# tesis_page2_arm.net
KiCad netlist of a schematic drawn in Altium Designer
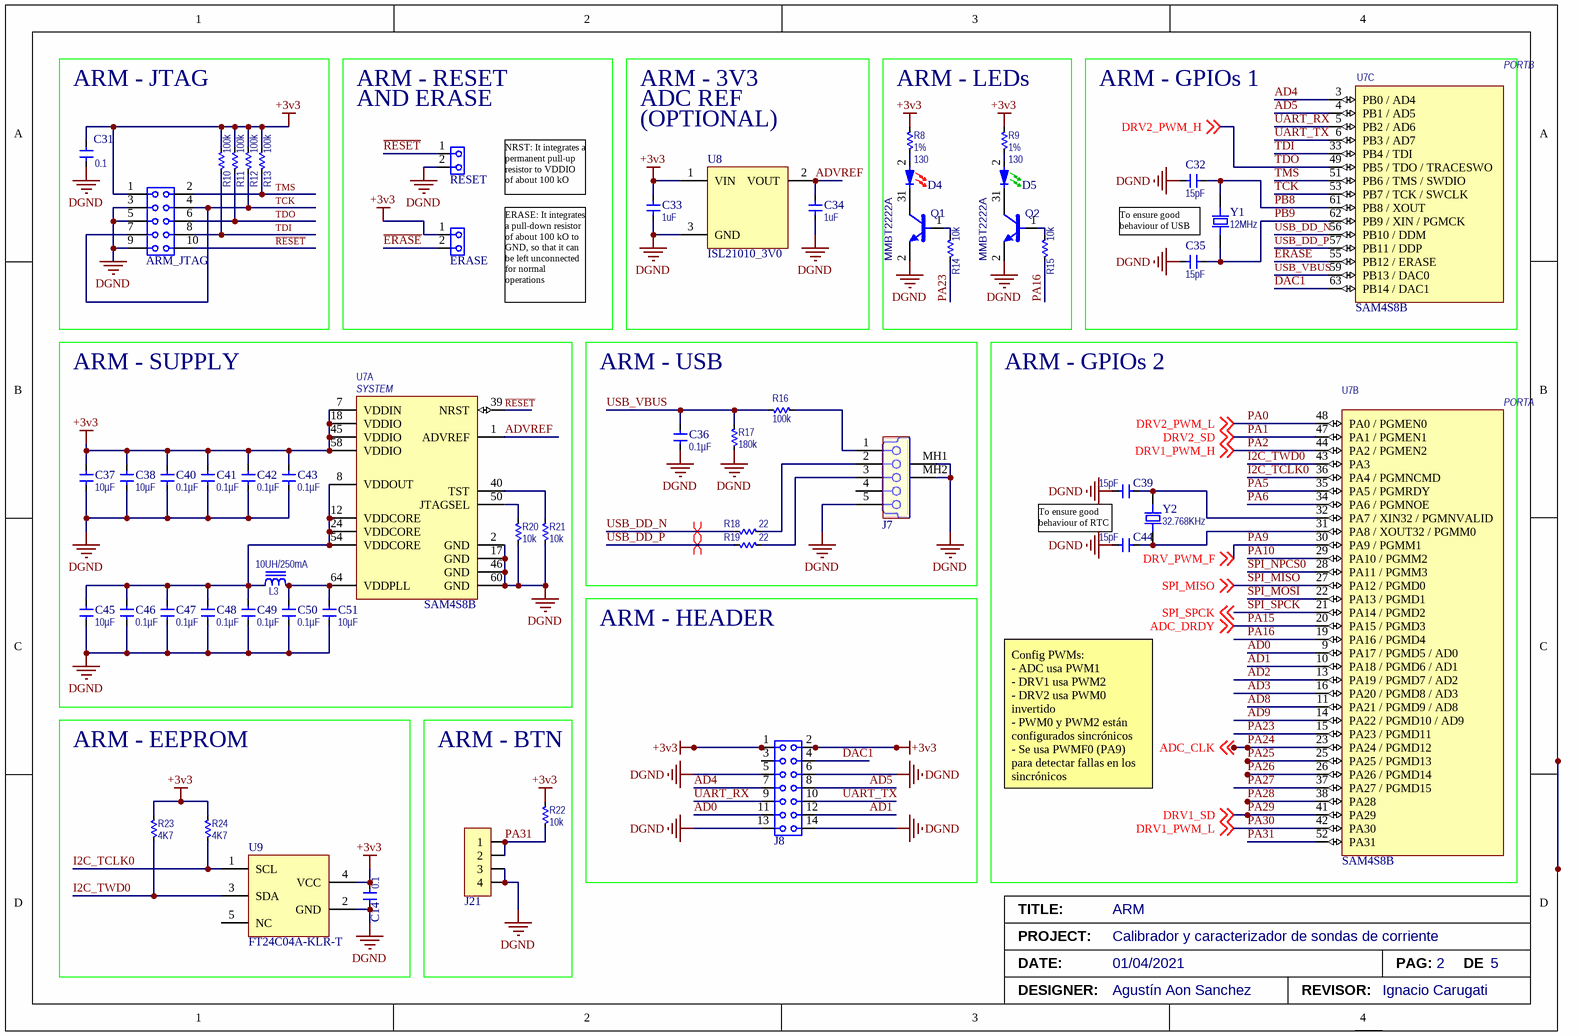
[diagram p0: tesis_page2_arm.SchDoc]

(export (version "E")
  (design (tool "Eeschema 10.0.6"))
  (components
    (comp (ref "ARM_JTAG")
      (value "CON_20021121-00010C4LF_FCI")
      (footprint "FCI_20021121-00010C4LF")
      (description "CONN HEADER 10POS DL UNSHRD SMD")
      (fields (field (name "MANUFACTURER") "FCI") (field (name "DIGIKEY PART NUMBER") "609-3695-1-ND"))
      (libsource (lib "pqm_v2_lib_connectors") (part "CON_20021121-00010C4LF_FCI"))
    )
    (comp (ref "C14")
      (value "0.1")
      (footprint "CAPC2013X110N")
      (description "CAP CER 0.1UF 25V 10% X7R 0805")
      (fields (field (name "MANUFACTURER") "Yageo") (field (name "TOLERANCE") "10%"))
      (libsource (lib "pqm_v2_lib_cap") (part "CAP_CC0805KRX7R8BB104_YAGEO"))
    )
    (comp (ref "C31")
      (value "0.1")
      (footprint "CAPC2013X110N")
      (description "CAP CER 0.1UF 25V 10% X7R 0805")
      (fields (field (name "MANUFACTURER") "Yageo") (field (name "TOLERANCE") "10%"))
      (libsource (lib "pqm_v2_lib_cap") (part "CAP_CC0805KRX7R8BB104_YAGEO"))
    )
    (comp (ref "C32")
      (value "15pF")
      (footprint "CAPC2013X110N")
      (description "CAP CER 15PF 50V NP0 0805")
      (fields (field (name "MANUFACTURER") "Kemet") (field (name "DIGIKEY PART NUMBER") "399-7428-1-ND"))
      (libsource (lib "pqm_v2_lib_cap") (part "CAP_C0805X150J5GACTU_KEMET"))
    )
    (comp (ref "C33")
      (value "1uF")
      (footprint "CAPC2013X110N")
      (description "CAP CER 1UF 16V X7R 0805")
      (fields (field (name "MANUFACTURER") "YAGEO") (field (name "TOLERANCE") "10%"))
      (libsource (lib "pqm_v2_lib_cap") (part "CAP_CC0805KKX7R7BB105_YAGEO"))
    )
    (comp (ref "C34")
      (value "1uF")
      (footprint "CAPC2013X110N")
      (description "CAP CER 1UF 16V X7R 0805")
      (fields (field (name "MANUFACTURER") "YAGEO") (field (name "TOLERANCE") "10%"))
      (libsource (lib "pqm_v2_lib_cap") (part "CAP_CC0805KKX7R7BB105_YAGEO"))
    )
    (comp (ref "C35")
      (value "15pF")
      (footprint "CAPC2013X110N")
      (description "CAP CER 15PF 50V NP0 0805")
      (fields (field (name "MANUFACTURER") "Kemet") (field (name "DIGIKEY PART NUMBER") "399-7428-1-ND"))
      (libsource (lib "pqm_v2_lib_cap") (part "CAP_C0805X150J5GACTU_KEMET"))
    )
    (comp (ref "C36")
      (value "0.1µF")
      (footprint "CAPC2013X110N")
      (description "CAP CER 0.1UF 25V 10% X7R 0805")
      (fields (field (name "MANUFACTURER") "Yageo") (field (name "TOLERANCE") "10%"))
      (libsource (lib "pqm_v2_lib_cap") (part "CAP_CC0805KRX7R8BB104_YAGEO"))
    )
    (comp (ref "C37")
      (value "10µF")
      (footprint "CAPC2013X110N")
      (description "CAP CER 10UF 16V X5R 0805")
      (fields (field (name "MANUFACTURER") "Samsung") (field (name "TOLERANCE") "10%"))
      (libsource (lib "lib_ic_CAP") (part "CAP_CL21A106KOCL3RC"))
    )
    (comp (ref "C38")
      (value "10µF")
      (footprint "CAPC2013X110N")
      (description "CAP CER 10UF 16V X5R 0805")
      (fields (field (name "MANUFACTURER") "Samsung") (field (name "TOLERANCE") "10%"))
      (libsource (lib "lib_ic_CAP") (part "CAP_CL21A106KOCL3RC"))
    )
    (comp (ref "C39")
      (value "15pF")
      (footprint "CAPC2013X110N")
      (description "CAP CER 15PF 50V NP0 0805")
      (fields (field (name "MANUFACTURER") "Kemet") (field (name "DIGIKEY PART NUMBER") "399-7428-1-ND"))
      (libsource (lib "pqm_v2_lib_cap") (part "CAP_C0805X150J5GACTU_KEMET"))
    )
    (comp (ref "C40")
      (value "0.1µF")
      (footprint "CAPC2013X110N")
      (description "CAP CER 0.1UF 25V 10% X7R 0805")
      (fields (field (name "MANUFACTURER") "Yageo") (field (name "TOLERANCE") "10%"))
      (libsource (lib "pqm_v2_lib_cap") (part "CAP_CC0805KRX7R8BB104_YAGEO"))
    )
    (comp (ref "C41")
      (value "0.1µF")
      (footprint "CAPC2013X110N")
      (description "CAP CER 0.1UF 25V 10% X7R 0805")
      (fields (field (name "MANUFACTURER") "Yageo") (field (name "TOLERANCE") "10%"))
      (libsource (lib "pqm_v2_lib_cap") (part "CAP_CC0805KRX7R8BB104_YAGEO"))
    )
    (comp (ref "C42")
      (value "0.1µF")
      (footprint "CAPC2013X110N")
      (description "CAP CER 0.1UF 25V 10% X7R 0805")
      (fields (field (name "MANUFACTURER") "Yageo") (field (name "TOLERANCE") "10%"))
      (libsource (lib "pqm_v2_lib_cap") (part "CAP_CC0805KRX7R8BB104_YAGEO"))
    )
    (comp (ref "C43")
      (value "0.1µF")
      (footprint "CAPC2013X110N")
      (description "CAP CER 0.1UF 25V 10% X7R 0805")
      (fields (field (name "MANUFACTURER") "Yageo") (field (name "TOLERANCE") "10%"))
      (libsource (lib "pqm_v2_lib_cap") (part "CAP_CC0805KRX7R8BB104_YAGEO"))
    )
    (comp (ref "C44")
      (value "15pF")
      (footprint "CAPC2013X110N")
      (description "CAP CER 15PF 50V NP0 0805")
      (fields (field (name "MANUFACTURER") "Kemet") (field (name "DIGIKEY PART NUMBER") "399-7428-1-ND"))
      (libsource (lib "pqm_v2_lib_cap") (part "CAP_C0805X150J5GACTU_KEMET"))
    )
    (comp (ref "C45")
      (value "10µF")
      (footprint "CAPC2013X110N")
      (description "CAP CER 10UF 16V X5R 0805")
      (fields (field (name "MANUFACTURER") "Samsung") (field (name "TOLERANCE") "10%"))
      (libsource (lib "lib_ic_CAP") (part "CAP_CL21A106KOCL3RC"))
    )
    (comp (ref "C46")
      (value "0.1µF")
      (footprint "CAPC2013X110N")
      (description "CAP CER 0.1UF 25V 10% X7R 0805")
      (fields (field (name "MANUFACTURER") "Yageo") (field (name "TOLERANCE") "10%"))
      (libsource (lib "pqm_v2_lib_cap") (part "CAP_CC0805KRX7R8BB104_YAGEO"))
    )
    (comp (ref "C47")
      (value "0.1µF")
      (footprint "CAPC2013X110N")
      (description "CAP CER 0.1UF 25V 10% X7R 0805")
      (fields (field (name "MANUFACTURER") "Yageo") (field (name "TOLERANCE") "10%"))
      (libsource (lib "pqm_v2_lib_cap") (part "CAP_CC0805KRX7R8BB104_YAGEO"))
    )
    (comp (ref "C48")
      (value "0.1µF")
      (footprint "CAPC2013X110N")
      (description "CAP CER 0.1UF 25V 10% X7R 0805")
      (fields (field (name "MANUFACTURER") "Yageo") (field (name "TOLERANCE") "10%"))
      (libsource (lib "pqm_v2_lib_cap") (part "CAP_CC0805KRX7R8BB104_YAGEO"))
    )
    (comp (ref "C49")
      (value "0.1µF")
      (footprint "CAPC2013X110N")
      (description "CAP CER 0.1UF 25V 10% X7R 0805")
      (fields (field (name "MANUFACTURER") "Yageo") (field (name "TOLERANCE") "10%"))
      (libsource (lib "pqm_v2_lib_cap") (part "CAP_CC0805KRX7R8BB104_YAGEO"))
    )
    (comp (ref "C50")
      (value "0.1µF")
      (footprint "CAPC2013X110N")
      (description "CAP CER 0.1UF 25V 10% X7R 0805")
      (fields (field (name "MANUFACTURER") "Yageo") (field (name "TOLERANCE") "10%"))
      (libsource (lib "pqm_v2_lib_cap") (part "CAP_CC0805KRX7R8BB104_YAGEO"))
    )
    (comp (ref "C51")
      (value "10µF")
      (footprint "CAPC2013X110N")
      (description "CAP CER 10UF 16V X5R 0805")
      (fields (field (name "MANUFACTURER") "Samsung") (field (name "TOLERANCE") "10%"))
      (libsource (lib "lib_ic_CAP") (part "CAP_CL21A106KOCL3RC"))
    )
    (comp (ref "D4")
      (value "DIO_150080RS75000_WURTH")
      (footprint "DIO0805")
      (description "LED RED CLEAR 0805 SMD")
      (fields
        (field (name "MANUFACTURER") "Wurth Electronics Inc.")
        (field (name "MANUFACTURER PART NUMBER") "150080RS75000")
      )
      (libsource (lib "lib_ic_DIO") (part "DIO_150080RS75000_WURTH"))
    )
    (comp (ref "D5")
      (value "DIO_150080VS75000_WURTH")
      (footprint "DIO0805")
      (description "LED GREEN CLEAR 0805 SMD")
      (fields
        (field (name "MANUFACTURER") "Wurth Electronics Inc.")
        (field (name "MANUFACTURER PART NUMBER") "150080VS75000")
      )
      (libsource (lib "lib_ic_DIO") (part "DIO_150080VS75000_WURTH"))
    )
    (comp (ref "ERASE")
      (value "CON_Header_1x2")
      (footprint "RAD2")
      (libsource (lib "lib_ic_CON") (part "CON_Header_1x2"))
    )
    (comp (ref "J7")
      (value "CON_MINI_USB")
      (footprint "UBS MiniB")
      (description "CONN RCPT MINI USB2.0 5POS SLD")
      (fields
        (field (name "DIGIKEY PART NUMBER") "H11589CT-ND")
        (field (name "MANUFACTURER PART NUMBER") "UX60SC-MB-5S8")
      )
      (libsource (lib "lib_ic_CON") (part "CON_MINI_USB"))
    )
    (comp (ref "J8")
      (value "CON_Header_CAL_1")
      (footprint "HeaderCAL_1")
      (libsource (lib "lib_ic_CON") (part "CON_Header_CAL_1"))
    )
    (comp (ref "J21")
      (value "MSC_B3F-1000_OMRON")
      (footprint "SW_1825910-6")
      (description "SWITCH TACTILE SPST-NO 0.05A 24V")
      (fields
        (field (name "MOUSER PART NUMBER") "653-B3F-1000")
        (field (name "MANUFACTURER PART NUMBER") "B3F-1000")
      )
      (libsource (lib "lib_ic_MSC") (part "MSC_B3F-1000_OMRON"))
    )
    (comp (ref "L3")
      (value "10UH/250mA")
      (footprint "INDC4532X170N")
      (description "FIXED IND 10UH 250mA 1.6 OHM SMD")
      (fields
        (field (name "MANUFACTURER") "Bourns Inc")
        (field (name "DIGIKEY PART NUMBER") "CM453232-100KLCT-ND")
      )
      (libsource (lib "lib_ic_MAG") (part "MAG_PM1812-100J-RC"))
    )
    (comp (ref "Q1")
      (value "MMBT2222A")
      (footprint "SOT23-3M")
      (description "TRANS NPN 40V 0.6A SMD SOT23-3")
      (fields
        (field (name "MOUSER PART NUMBER") "621-MMBT2222A-F")
        (field (name "DIGIKEY PART NUMBER") "MMBT2222A-7-F")
      )
      (libsource (lib "lib_ic_TRAN") (part "Q_MMBT2222A-7-F_DIODES"))
    )
    (comp (ref "Q2")
      (value "MMBT2222A")
      (footprint "SOT23-3M")
      (description "TRANS NPN 40V 0.6A SMD SOT23-3")
      (fields
        (field (name "MOUSER PART NUMBER") "621-MMBT2222A-F")
        (field (name "DIGIKEY PART NUMBER") "MMBT2222A-7-F")
      )
      (libsource (lib "lib_ic_TRAN") (part "Q_MMBT2222A-7-F_DIODES"))
    )
    (comp (ref "R8")
      (value "130")
      (footprint "RESC2013X065BN")
      (description "RES SMD 130 OHM 1% 1/8W 0805")
      (fields
        (field (name "MANUFACTURER") "Yageo")
        (field (name "DIGIKEY PART NUMBER") "311-130CRCT-ND")
        (field (name "TOLERANCE") "1%")
      )
      (libsource (lib "lib_ic_RES") (part "RES_RC0805FR-07130RL_YAGEO"))
    )
    (comp (ref "R9")
      (value "130")
      (footprint "RESC2013X065BN")
      (description "RES SMD 130 OHM 1% 1/8W 0805")
      (fields
        (field (name "MANUFACTURER") "Yageo")
        (field (name "DIGIKEY PART NUMBER") "311-130CRCT-ND")
        (field (name "TOLERANCE") "1%")
      )
      (libsource (lib "lib_ic_RES") (part "RES_RC0805FR-07130RL_YAGEO"))
    )
    (comp (ref "R10")
      (value "100k")
      (footprint "RESC2013X065BN")
      (description "RES SMD 100K OHM 5% 1/8W 0805")
      (fields (field (name "TOLERANCE") "5%") (field (name "MANUFACTURER") "Yageo"))
      (libsource (lib "pqm_v2_lib_res") (part "RES_AC0805JR-07100KL_YAGEO"))
    )
    (comp (ref "R11")
      (value "100k")
      (footprint "RESC2013X065BN")
      (description "RES SMD 100K OHM 5% 1/8W 0805")
      (fields (field (name "TOLERANCE") "5%") (field (name "MANUFACTURER") "Yageo"))
      (libsource (lib "pqm_v2_lib_res") (part "RES_AC0805JR-07100KL_YAGEO"))
    )
    (comp (ref "R12")
      (value "100k")
      (footprint "RESC2013X065BN")
      (description "RES SMD 100K OHM 5% 1/8W 0805")
      (fields (field (name "TOLERANCE") "5%") (field (name "MANUFACTURER") "Yageo"))
      (libsource (lib "pqm_v2_lib_res") (part "RES_AC0805JR-07100KL_YAGEO"))
    )
    (comp (ref "R13")
      (value "100k")
      (footprint "RESC2013X065BN")
      (description "RES SMD 100K OHM 5% 1/8W 0805")
      (fields (field (name "TOLERANCE") "5%") (field (name "MANUFACTURER") "Yageo"))
      (libsource (lib "pqm_v2_lib_res") (part "RES_AC0805JR-07100KL_YAGEO"))
    )
    (comp (ref "R14")
      (value "10k")
      (footprint "RESC2013X065BN")
      (description "RES SMD 10K OHM 1% 1/8W 0805")
      (fields (field (name "MANUFACTURER") "Yageo") (field (name "DIGIKEY PART NUMBER") "311-10.0KCRCT-ND"))
      (libsource (lib "lib_ic_RES") (part "RES_RC0805FR-0710KL_YAGEO"))
    )
    (comp (ref "R15")
      (value "10k")
      (footprint "RESC2013X065BN")
      (description "RES SMD 10K OHM 1% 1/8W 0805")
      (fields (field (name "MANUFACTURER") "Yageo") (field (name "DIGIKEY PART NUMBER") "311-10.0KCRCT-ND"))
      (libsource (lib "lib_ic_RES") (part "RES_RC0805FR-0710KL_YAGEO"))
    )
    (comp (ref "R16")
      (value "100k")
      (footprint "RESC3216N")
      (description "RES SMD 100K OHM 5% 1/4W 1206")
      (fields (field (name "MANUFACTURER") "YAGEO") (field (name "TOLERANCE") "5%"))
      (libsource (lib "lib_ic_RES") (part "RES_RC1206JR-07100KL_YAGEO"))
    )
    (comp (ref "R17")
      (value "180k")
      (footprint "RESC3216N")
      (description "RES SMD 180K OHM 5% 1/4W 1206")
      (fields (field (name "MANUFACTURER") "YAGEO") (field (name "TOLERANCE") "5%"))
      (libsource (lib "lib_ic_RES") (part "RES_RC1206JR-07180KL_YAGEO"))
    )
    (comp (ref "R18")
      (value "22")
      (footprint "RESC2013X065BN")
      (description "RES SMD 22 OHM 5% 1/8W 0805")
      (fields (field (name "MANUFACTURER") "Yageo") (field (name "TOLERANCE") "5%"))
      (libsource (lib "lib_ic_RES") (part "RES_AC0805JR-0722RL_YAGEO"))
    )
    (comp (ref "R19")
      (value "22")
      (footprint "RESC2013X065BN")
      (description "RES SMD 22 OHM 5% 1/8W 0805")
      (fields (field (name "MANUFACTURER") "Yageo") (field (name "TOLERANCE") "5%"))
      (libsource (lib "lib_ic_RES") (part "RES_AC0805JR-0722RL_YAGEO"))
    )
    (comp (ref "R20")
      (value "10k")
      (footprint "RESC2013X065BN")
      (description "RES SMD 10K OHM 5% 1/8W 0805")
      (fields (field (name "TOLERANCE") "5%") (field (name "MANUFACTURER") "Yageo"))
      (libsource (lib "pqm_v2_lib_res") (part "RES_RC0805JR-0710KL_YAGEO"))
    )
    (comp (ref "R21")
      (value "10k")
      (footprint "RESC2013X065BN")
      (description "RES SMD 10K OHM 5% 1/8W 0805")
      (fields (field (name "TOLERANCE") "5%") (field (name "MANUFACTURER") "Yageo"))
      (libsource (lib "pqm_v2_lib_res") (part "RES_RC0805JR-0710KL_YAGEO"))
    )
    (comp (ref "R22")
      (value "10k")
      (footprint "RESC2013X065BN")
      (description "RES SMD 10K OHM 5% 1/8W 0805")
      (fields (field (name "TOLERANCE") "5%") (field (name "MANUFACTURER") "Yageo"))
      (libsource (lib "pqm_v2_lib_res") (part "RES_RC0805JR-0710KL_YAGEO"))
    )
    (comp (ref "R23")
      (value "4K7")
      (footprint "RESC2013X065BN")
      (description "RES SMD 4.7K OHM 1% 1/8W 0805")
      (fields (field (name "MANUFACTURER") "Yageo") (field (name "DIGIKEY PART NUMBER") "311-4.70KCRCT-ND"))
      (libsource (lib "lib_ic_RES") (part "RES_RC0805FR-074K7L_YAGEO"))
    )
    (comp (ref "R24")
      (value "4K7")
      (footprint "RESC2013X065BN")
      (description "RES SMD 4.7K OHM 1% 1/8W 0805")
      (fields (field (name "MANUFACTURER") "Yageo") (field (name "DIGIKEY PART NUMBER") "311-4.70KCRCT-ND"))
      (libsource (lib "lib_ic_RES") (part "RES_RC0805FR-074K7L_YAGEO"))
    )
    (comp (ref "RESET")
      (value "CON_Header_1x2")
      (footprint "RAD2")
      (libsource (lib "lib_ic_CON") (part "CON_Header_1x2"))
    )
    (comp (ref "U7")
      (value "SAM4S8B")
      (footprint "TQFP50P1000X1000X160-64N")
      (description "IC MCU 32BIT 512KB FLASH 64LQFP")
      (fields (field (name "MANUFACTURER") "Atmel") (field (name "DIGIKEY PART NUMBER") "ATSAM4S8BA-AU-ND"))
      (libsource (lib "") (part "IC_ATSAM4S8BA-AU_ATMEL_1"))
    )
    (comp (ref "U8")
      (value "ISL21010_3V0")
      (footprint "SOT23-3M")
      (description "IC VREF SERIES 3V SOT23-3")
      (fields
        (field (name "DIGIKEY PART NUMBER") "ISL21010CFH330Z-TKCT-ND")
        (field (name "MANUFACTURER PART NUMBER") "ISL21010CFH330Z-TK")
      )
      (libsource (lib "lib_ic_IC") (part "IC_ISL21010_3V0_INTERSIL"))
    )
    (comp (ref "U9")
      (value "FT24C04A-KLR-T")
      (footprint "SOT23-5AM")
      (fields (field (name "MANUFACTURER") "Fremont Micro Devices"))
      (libsource (lib "lib_ic_IC") (part "IC_FT24C04A-KLR-T"))
    )
    (comp (ref "Y1")
      (value "12MHz")
      (footprint "CSM-3X")
      (description "12 MHz ±30 ppm Cristales 20 pF 60 Ohm -10°C ~ 70°C Montaje en superficie HC49/US")
      (fields (field (name "MANUFACTURER") "ECS Inc.") (field (name "DIGIKEY PART NUMBER") "XC1770DKR-ND"))
      (libsource (lib "pqm_v2_lib_connectors") (part "MSC_ECS-120-20-3X-TR_ECS"))
    )
    (comp (ref "Y2")
      (value "32.768KHz")
      (footprint "XTAL3215X090N")
      (description "CRYSTAL 32.7680KHZ 12.5PF SMD")
      (fields (field (name "MANUFACTURER") "ECS") (field (name "DIGIKEY PART NUMBER") "XC1967CT-ND"))
      (libsource (lib "pqm_v2_lib_connectors") (part "MSC_ECS-.327-12.5-34S-TR_ECS"))
    )
  )
  (nets
    (net (code "1") (name "+3v3") (class "Default")
      (node (ref "ARM_JTAG") (pin "1") (pinfunction "1_1") (pintype "passive"))
      (node (ref "C14") (pin "2") (pinfunction "T2_2") (pintype "passive"))
      (node (ref "C31") (pin "1") (pinfunction "T1_1") (pintype "passive"))
      (node (ref "C33") (pin "1") (pinfunction "T1_1") (pintype "passive"))
      (node (ref "C37") (pin "2") (pinfunction "T2_2") (pintype "passive"))
      (node (ref "C38") (pin "2") (pinfunction "T2_2") (pintype "passive"))
      (node (ref "C40") (pin "2") (pinfunction "T2_2") (pintype "passive"))
      (node (ref "C41") (pin "2") (pinfunction "T2_2") (pintype "passive"))
      (node (ref "C42") (pin "2") (pinfunction "T2_2") (pintype "passive"))
      (node (ref "C43") (pin "2") (pinfunction "T2_2") (pintype "passive"))
      (node (ref "ERASE") (pin "1") (pinfunction "1_1") (pintype "passive"))
      (node (ref "J8") (pin "1") (pinfunction "1_1") (pintype "passive"))
      (node (ref "J8") (pin "2") (pinfunction "2_2") (pintype "passive"))
      (node (ref "R10") (pin "2") (pinfunction "T2_2") (pintype "passive"))
      (node (ref "R11") (pin "2") (pinfunction "T2_2") (pintype "passive"))
      (node (ref "R12") (pin "2") (pinfunction "T2_2") (pintype "passive"))
      (node (ref "R13") (pin "2") (pinfunction "T2_2") (pintype "passive"))
      (node (ref "R22") (pin "2") (pinfunction "T2_2") (pintype "passive"))
      (node (ref "R23") (pin "2") (pinfunction "T2_2") (pintype "passive"))
      (node (ref "R24") (pin "2") (pinfunction "T2_2") (pintype "passive"))
      (node (ref "R8") (pin "2") (pinfunction "T2_2") (pintype "passive"))
      (node (ref "R9") (pin "2") (pinfunction "T2_2") (pintype "passive"))
      (node (ref "U7") (pin "18") (pinfunction "VDDIO_18") (pintype "power_in"))
      (node (ref "U7") (pin "45") (pinfunction "VDDIO_45") (pintype "power_in"))
      (node (ref "U7") (pin "58") (pinfunction "VDDIO_58") (pintype "power_in"))
      (node (ref "U7") (pin "7") (pinfunction "VDDIN_7") (pintype "power_in"))
      (node (ref "U8") (pin "1") (pinfunction "VIN_1") (pintype "passive"))
      (node (ref "U9") (pin "4") (pinfunction "VCC_4") (pintype "passive"))
    )
    (net (code "2") (name "/AD0") (class "Default")
      (node (ref "J8") (pin "11") (pinfunction "11_11") (pintype "passive"))
      (node (ref "U7") (pin "9") (pinfunction "PA17_/_PGMD5_/_AD0_9") (pintype "bidirectional"))
    )
    (net (code "3") (name "/AD1") (class "Default")
      (node (ref "J8") (pin "12") (pinfunction "12_12") (pintype "passive"))
      (node (ref "U7") (pin "10") (pinfunction "PA18_/_PGMD6_/_AD1_10") (pintype "bidirectional"))
    )
    (net (code "4") (name "/AD2") (class "Default")
      (node (ref "U7") (pin "13") (pinfunction "PA19_/_PGMD7_/_AD2_13") (pintype "bidirectional"))
    )
    (net (code "5") (name "/AD3") (class "Default")
      (node (ref "U7") (pin "16") (pinfunction "PA20_/_PGMD8_/_AD3_16") (pintype "bidirectional"))
    )
    (net (code "6") (name "/AD4") (class "Default")
      (node (ref "J8") (pin "7") (pinfunction "7_7") (pintype "passive"))
      (node (ref "U7") (pin "3") (pinfunction "PB0_/_AD4_3") (pintype "bidirectional"))
    )
    (net (code "7") (name "/AD5") (class "Default")
      (node (ref "J8") (pin "8") (pinfunction "8_8") (pintype "passive"))
      (node (ref "U7") (pin "4") (pinfunction "PB1_/_AD5_4") (pintype "bidirectional"))
    )
    (net (code "8") (name "/AD8") (class "Default")
      (node (ref "U7") (pin "11") (pinfunction "PA21_/_PGMD9_/_AD8_11") (pintype "bidirectional"))
    )
    (net (code "9") (name "/AD9") (class "Default")
      (node (ref "U7") (pin "14") (pinfunction "PA22_/_PGMD10_/_AD9_14") (pintype "bidirectional"))
    )
    (net (code "10") (name "/ADVREF") (class "Default")
      (node (ref "C34") (pin "1") (pinfunction "T1_1") (pintype "passive"))
      (node (ref "U7") (pin "1") (pinfunction "ADVREF_1") (pintype "power_in"))
      (node (ref "U8") (pin "2") (pinfunction "VOUT_2") (pintype "passive"))
    )
    (net (code "11") (name "/DAC1") (class "Default")
      (node (ref "J8") (pin "4") (pinfunction "4_4") (pintype "passive"))
      (node (ref "U7") (pin "63") (pinfunction "PB14_/_DAC1_63") (pintype "bidirectional"))
    )
    (net (code "12") (name "/I2C_TCLK0") (class "Default")
      (node (ref "R24") (pin "1") (pinfunction "T1_1") (pintype "passive"))
      (node (ref "U7") (pin "36") (pinfunction "PA4_/_PGMNCMD_36") (pintype "bidirectional"))
      (node (ref "U9") (pin "1") (pinfunction "SCL_1") (pintype "passive"))
    )
    (net (code "13") (name "/I2C_TWD0") (class "Default")
      (node (ref "R23") (pin "1") (pinfunction "T1_1") (pintype "passive"))
      (node (ref "U7") (pin "43") (pinfunction "PA3_43") (pintype "bidirectional"))
      (node (ref "U9") (pin "3") (pinfunction "SDA_3") (pintype "passive"))
    )
    (net (code "14") (name "/PA5") (class "Default")
      (node (ref "U7") (pin "35") (pinfunction "PA5_/_PGMRDY_35") (pintype "bidirectional"))
    )
    (net (code "15") (name "/PA6") (class "Default")
      (node (ref "U7") (pin "34") (pinfunction "PA6_/_PGMNOE_34") (pintype "bidirectional"))
    )
    (net (code "16") (name "/PA10") (class "Default")
      (node (ref "U7") (pin "29") (pinfunction "PA10_/_PGMM2_29") (pintype "bidirectional"))
    )
    (net (code "17") (name "/PA16") (class "Default")
      (node (ref "R15") (pin "2") (pinfunction "T2_2") (pintype "passive"))
      (node (ref "U7") (pin "19") (pinfunction "PA16_/_PGMD4_19") (pintype "bidirectional"))
    )
    (net (code "18") (name "/PA23") (class "Default")
      (node (ref "R14") (pin "2") (pinfunction "T2_2") (pintype "passive"))
      (node (ref "U7") (pin "15") (pinfunction "PA23_/_PGMD11_15") (pintype "bidirectional"))
    )
    (net (code "19") (name "/PA25") (class "Default")
      (node (ref "U7") (pin "25") (pinfunction "PA25_/_PGMD13_25") (pintype "bidirectional"))
    )
    (net (code "20") (name "/PA26") (class "Default")
      (node (ref "U7") (pin "26") (pinfunction "PA26_/_PGMD14_26") (pintype "bidirectional"))
    )
    (net (code "21") (name "/PA27") (class "Default")
      (node (ref "U7") (pin "37") (pinfunction "PA27_/_PGMD15_37") (pintype "bidirectional"))
    )
    (net (code "22") (name "/PA28") (class "Default")
      (node (ref "U7") (pin "38") (pinfunction "PA28_38") (pintype "bidirectional"))
    )
    (net (code "23") (name "/PA31") (class "Default")
      (node (ref "J21") (pin "1") (pinfunction "1_1") (pintype "passive"))
      (node (ref "J21") (pin "2") (pinfunction "2_2") (pintype "passive"))
      (node (ref "R22") (pin "1") (pinfunction "T1_1") (pintype "passive"))
      (node (ref "U7") (pin "52") (pinfunction "PA31_52") (pintype "bidirectional"))
    )
    (net (code "24") (name "/PB8") (class "Default")
      (node (ref "C32") (pin "1") (pinfunction "T1_1") (pintype "passive"))
      (node (ref "U7") (pin "61") (pinfunction "PB8_/_XOUT_61") (pintype "bidirectional"))
      (node (ref "Y1") (pin "2") (pinfunction "2_2") (pintype "passive"))
    )
    (net (code "25") (name "/PB9") (class "Default")
      (node (ref "C35") (pin "2") (pinfunction "T2_2") (pintype "passive"))
      (node (ref "U7") (pin "62") (pinfunction "PB9_/_XIN_/_PGMCK_62") (pintype "bidirectional"))
      (node (ref "Y1") (pin "1") (pinfunction "1_1") (pintype "passive"))
    )
    (net (code "26") (name "/SPI_MOSI") (class "Default")
      (node (ref "U7") (pin "22") (pinfunction "PA13_/_PGMD1_22") (pintype "bidirectional"))
    )
    (net (code "27") (name "/SPI_NPCS0") (class "Default")
      (node (ref "U7") (pin "28") (pinfunction "PA11_/_PGMM3_28") (pintype "bidirectional"))
    )
    (net (code "28") (name "/TCK") (class "Default")
      (node (ref "ARM_JTAG") (pin "4") (pinfunction "4_4") (pintype "passive"))
      (node (ref "ARM_JTAG") (pin "7") (pinfunction "7_7") (pintype "passive"))
      (node (ref "R12") (pin "1") (pinfunction "T1_1") (pintype "passive"))
      (node (ref "U7") (pin "53") (pinfunction "PB7_/_TCK_/_SWCLK_53") (pintype "bidirectional"))
    )
    (net (code "29") (name "/TDI") (class "Default")
      (node (ref "ARM_JTAG") (pin "8") (pinfunction "8_8") (pintype "passive"))
      (node (ref "R10") (pin "1") (pinfunction "T1_1") (pintype "passive"))
      (node (ref "U7") (pin "33") (pinfunction "PB4_/_TDI_33") (pintype "bidirectional"))
    )
    (net (code "30") (name "/TMS") (class "Default")
      (node (ref "ARM_JTAG") (pin "2") (pinfunction "2_2") (pintype "passive"))
      (node (ref "R13") (pin "1") (pinfunction "T1_1") (pintype "passive"))
      (node (ref "U7") (pin "51") (pinfunction "PB6_/_TMS_/_SWDIO_51") (pintype "bidirectional"))
    )
    (net (code "31") (name "/UART_RX") (class "Default")
      (node (ref "J8") (pin "9") (pinfunction "9_9") (pintype "passive"))
      (node (ref "U7") (pin "5") (pinfunction "PB2_/_AD6_5") (pintype "bidirectional"))
    )
    (net (code "32") (name "/UART_TX") (class "Default")
      (node (ref "J8") (pin "10") (pinfunction "10_10") (pintype "passive"))
      (node (ref "U7") (pin "6") (pinfunction "PB3_/_AD7_6") (pintype "bidirectional"))
    )
    (net (code "33") (name "/USB_DD_N") (class "Default")
      (node (ref "R18") (pin "2") (pinfunction "T2_2") (pintype "passive"))
      (node (ref "U7") (pin "56") (pinfunction "PB10_/_DDM_56") (pintype "bidirectional"))
    )
    (net (code "34") (name "/USB_DD_P") (class "Default")
      (node (ref "R19") (pin "2") (pinfunction "T2_2") (pintype "passive"))
      (node (ref "U7") (pin "57") (pinfunction "PB11_/_DDP_57") (pintype "bidirectional"))
    )
    (net (code "35") (name "/USB_VBUS") (class "Default")
      (node (ref "C36") (pin "2") (pinfunction "T2_2") (pintype "passive"))
      (node (ref "R16") (pin "2") (pinfunction "T2_2") (pintype "passive"))
      (node (ref "R17") (pin "1") (pinfunction "T1_1") (pintype "passive"))
      (node (ref "U7") (pin "59") (pinfunction "PB13_/_DAC0_59") (pintype "bidirectional"))
    )
    (net (code "36") (name "/~{ERASE}") (class "Default")
      (node (ref "ERASE") (pin "2") (pinfunction "2_2") (pintype "passive"))
      (node (ref "U7") (pin "55") (pinfunction "PB12_/_ERASE_55") (pintype "bidirectional"))
    )
    (net (code "37") (name "/~{RESET}") (class "Default")
      (node (ref "ARM_JTAG") (pin "10") (pinfunction "10_10") (pintype "passive"))
      (node (ref "RESET") (pin "1") (pinfunction "1_1") (pintype "passive"))
      (node (ref "U7") (pin "39") (pinfunction "NRST_39") (pintype "bidirectional"))
    )
    (net (code "38") (name "ADC_CLK") (class "Default")
      (node (ref "U7") (pin "23") (pinfunction "PA24_/_PGMD12_23") (pintype "bidirectional"))
    )
    (net (code "39") (name "ADC_DRDY") (class "Default")
      (node (ref "U7") (pin "20") (pinfunction "PA15_/_PGMD3_20") (pintype "bidirectional"))
    )
    (net (code "40") (name "DGND") (class "Default")
      (node (ref "ARM_JTAG") (pin "3") (pinfunction "3_3") (pintype "passive"))
      (node (ref "ARM_JTAG") (pin "5") (pinfunction "5_5") (pintype "passive"))
      (node (ref "ARM_JTAG") (pin "9") (pinfunction "9_9") (pintype "passive"))
      (node (ref "C14") (pin "1") (pinfunction "T1_1") (pintype "passive"))
      (node (ref "C31") (pin "2") (pinfunction "T2_2") (pintype "passive"))
      (node (ref "C32") (pin "2") (pinfunction "T2_2") (pintype "passive"))
      (node (ref "C33") (pin "2") (pinfunction "T2_2") (pintype "passive"))
      (node (ref "C34") (pin "2") (pinfunction "T2_2") (pintype "passive"))
      (node (ref "C35") (pin "1") (pinfunction "T1_1") (pintype "passive"))
      (node (ref "C36") (pin "1") (pinfunction "T1_1") (pintype "passive"))
      (node (ref "C37") (pin "1") (pinfunction "T1_1") (pintype "passive"))
      (node (ref "C38") (pin "1") (pinfunction "T1_1") (pintype "passive"))
      (node (ref "C39") (pin "2") (pinfunction "T2_2") (pintype "passive"))
      (node (ref "C40") (pin "1") (pinfunction "T1_1") (pintype "passive"))
      (node (ref "C41") (pin "1") (pinfunction "T1_1") (pintype "passive"))
      (node (ref "C42") (pin "1") (pinfunction "T1_1") (pintype "passive"))
      (node (ref "C43") (pin "1") (pinfunction "T1_1") (pintype "passive"))
      (node (ref "C44") (pin "2") (pinfunction "T2_2") (pintype "passive"))
      (node (ref "C45") (pin "1") (pinfunction "T1_1") (pintype "passive"))
      (node (ref "C46") (pin "2") (pinfunction "T2_2") (pintype "passive"))
      (node (ref "C47") (pin "2") (pinfunction "T2_2") (pintype "passive"))
      (node (ref "C48") (pin "2") (pinfunction "T2_2") (pintype "passive"))
      (node (ref "C49") (pin "2") (pinfunction "T2_2") (pintype "passive"))
      (node (ref "C50") (pin "1") (pinfunction "T1_1") (pintype "passive"))
      (node (ref "C51") (pin "2") (pinfunction "T2_2") (pintype "passive"))
      (node (ref "J21") (pin "3") (pinfunction "3_3") (pintype "passive"))
      (node (ref "J21") (pin "4") (pinfunction "4_4") (pintype "passive"))
      (node (ref "J7") (pin "5") (pinfunction "5_5") (pintype "passive"))
      (node (ref "J7") (pin "MH1") (pinfunction "MH1_MH1") (pintype "passive"))
      (node (ref "J7") (pin "MH2") (pinfunction "MH2_MH2") (pintype "passive"))
      (node (ref "J8") (pin "13") (pinfunction "13_13") (pintype "passive"))
      (node (ref "J8") (pin "14") (pinfunction "14_14") (pintype "passive"))
      (node (ref "J8") (pin "5") (pinfunction "5_5") (pintype "passive"))
      (node (ref "J8") (pin "6") (pinfunction "6_6") (pintype "passive"))
      (node (ref "Q1") (pin "2") (pinfunction "E_2") (pintype "passive"))
      (node (ref "Q2") (pin "2") (pinfunction "E_2") (pintype "passive"))
      (node (ref "R17") (pin "2") (pinfunction "T2_2") (pintype "passive"))
      (node (ref "R20") (pin "1") (pinfunction "T1_1") (pintype "passive"))
      (node (ref "R21") (pin "1") (pinfunction "T1_1") (pintype "passive"))
      (node (ref "RESET") (pin "2") (pinfunction "2_2") (pintype "passive"))
      (node (ref "U7") (pin "17") (pinfunction "GND_17") (pintype "power_in"))
      (node (ref "U7") (pin "2") (pinfunction "GND_2") (pintype "power_in"))
      (node (ref "U7") (pin "46") (pinfunction "GND_46") (pintype "power_in"))
      (node (ref "U7") (pin "60") (pinfunction "GND_60") (pintype "power_in"))
      (node (ref "U8") (pin "3") (pinfunction "GND_3") (pintype "passive"))
      (node (ref "U9") (pin "2") (pinfunction "GND_2") (pintype "passive"))
    )
    (net (code "41") (name "DRV1_PWM_H") (class "Default")
      (node (ref "U7") (pin "44") (pinfunction "PA2_/_PGMEN2_44") (pintype "bidirectional"))
    )
    (net (code "42") (name "DRV1_PWM_L") (class "Default")
      (node (ref "U7") (pin "42") (pinfunction "PA30_42") (pintype "bidirectional"))
    )
    (net (code "43") (name "DRV1_SD") (class "Default")
      (node (ref "U7") (pin "41") (pinfunction "PA29_41") (pintype "bidirectional"))
    )
    (net (code "44") (name "DRV2_PWM_H") (class "Default")
      (node (ref "ARM_JTAG") (pin "6") (pinfunction "6_6") (pintype "passive"))
      (node (ref "R11") (pin "1") (pinfunction "T1_1") (pintype "passive"))
      (node (ref "U7") (pin "49") (pinfunction "PB5_/_TDO_/_TRACESWO_49") (pintype "bidirectional"))
    )
    (net (code "45") (name "DRV2_PWM_L") (class "Default")
      (node (ref "U7") (pin "48") (pinfunction "PA0_/_PGMEN0_48") (pintype "bidirectional"))
    )
    (net (code "46") (name "DRV2_SD") (class "Default")
      (node (ref "U7") (pin "47") (pinfunction "PA1_/_PGMEN1_47") (pintype "bidirectional"))
    )
    (net (code "47") (name "DRV_PWM_F") (class "Default")
      (node (ref "U7") (pin "30") (pinfunction "PA9_/_PGMM1_30") (pintype "bidirectional"))
    )
    (net (code "48") (name "Net-(C39-T1)") (class "Default")
      (node (ref "C39") (pin "1") (pinfunction "T1_1") (pintype "passive"))
      (node (ref "U7") (pin "32") (pinfunction "PA7_/_XIN32_/_PGMNVALID_32") (pintype "bidirectional"))
      (node (ref "Y2") (pin "2") (pinfunction "2_2") (pintype "passive"))
    )
    (net (code "49") (name "Net-(C44-T1)") (class "Default")
      (node (ref "C44") (pin "1") (pinfunction "T1_1") (pintype "passive"))
      (node (ref "U7") (pin "31") (pinfunction "PA8_/_XOUT32_/_PGMM0_31") (pintype "bidirectional"))
      (node (ref "Y2") (pin "1") (pinfunction "1_1") (pintype "passive"))
    )
    (net (code "50") (name "Net-(C45-T2)") (class "Default")
      (node (ref "C45") (pin "2") (pinfunction "T2_2") (pintype "passive"))
      (node (ref "C46") (pin "1") (pinfunction "T1_1") (pintype "passive"))
      (node (ref "C47") (pin "1") (pinfunction "T1_1") (pintype "passive"))
      (node (ref "C48") (pin "1") (pinfunction "T1_1") (pintype "passive"))
      (node (ref "C49") (pin "1") (pinfunction "T1_1") (pintype "passive"))
      (node (ref "L3") (pin "1") (pinfunction "1_1") (pintype "passive"))
      (node (ref "U7") (pin "12") (pinfunction "VDDCORE_12") (pintype "power_in"))
      (node (ref "U7") (pin "24") (pinfunction "VDDCORE_24") (pintype "power_in"))
      (node (ref "U7") (pin "54") (pinfunction "VDDCORE_54") (pintype "power_in"))
      (node (ref "U7") (pin "8") (pinfunction "VDDOUT_8") (pintype "power_in"))
    )
    (net (code "51") (name "Net-(C50-T2)") (class "Default")
      (node (ref "C50") (pin "2") (pinfunction "T2_2") (pintype "passive"))
      (node (ref "C51") (pin "1") (pinfunction "T1_1") (pintype "passive"))
      (node (ref "L3") (pin "2") (pinfunction "2_2") (pintype "passive"))
      (node (ref "U7") (pin "64") (pinfunction "VDDPLL_64") (pintype "power_in"))
    )
    (net (code "52") (name "Net-(D4-Anode)") (class "Default")
      (node (ref "D4") (pin "2") (pinfunction "Anode_2") (pintype "passive"))
      (node (ref "R8") (pin "1") (pinfunction "T1_1") (pintype "passive"))
    )
    (net (code "53") (name "Net-(D4-Cathode)") (class "Default")
      (node (ref "D4") (pin "1") (pinfunction "Cathode_1") (pintype "passive"))
      (node (ref "Q1") (pin "3") (pinfunction "C_3") (pintype "passive"))
    )
    (net (code "54") (name "Net-(D5-Anode)") (class "Default")
      (node (ref "D5") (pin "2") (pinfunction "Anode_2") (pintype "passive"))
      (node (ref "R9") (pin "1") (pinfunction "T1_1") (pintype "passive"))
    )
    (net (code "55") (name "Net-(D5-Cathode)") (class "Default")
      (node (ref "D5") (pin "1") (pinfunction "Cathode_1") (pintype "passive"))
      (node (ref "Q2") (pin "3") (pinfunction "C_3") (pintype "passive"))
    )
    (net (code "56") (name "Net-(Q1-B)") (class "Default")
      (node (ref "Q1") (pin "1") (pinfunction "B_1") (pintype "passive"))
      (node (ref "R14") (pin "1") (pinfunction "T1_1") (pintype "passive"))
    )
    (net (code "57") (name "Net-(Q2-B)") (class "Default")
      (node (ref "Q2") (pin "1") (pinfunction "B_1") (pintype "passive"))
      (node (ref "R15") (pin "1") (pinfunction "T1_1") (pintype "passive"))
    )
    (net (code "58") (name "Net-(R16-T1)") (class "Default")
      (node (ref "J7") (pin "1") (pinfunction "1_1") (pintype "passive"))
      (node (ref "R16") (pin "1") (pinfunction "T1_1") (pintype "passive"))
    )
    (net (code "59") (name "Net-(R18-T1)") (class "Default")
      (node (ref "J7") (pin "2") (pinfunction "2_2") (pintype "passive"))
      (node (ref "R18") (pin "1") (pinfunction "T1_1") (pintype "passive"))
    )
    (net (code "60") (name "Net-(R19-T1)") (class "Default")
      (node (ref "J7") (pin "3") (pinfunction "3_3") (pintype "passive"))
      (node (ref "R19") (pin "1") (pinfunction "T1_1") (pintype "passive"))
    )
    (net (code "61") (name "Net-(R20-T2)") (class "Default")
      (node (ref "R20") (pin "2") (pinfunction "T2_2") (pintype "passive"))
      (node (ref "U7") (pin "50") (pinfunction "JTAGSEL_50") (pintype "passive"))
    )
    (net (code "62") (name "Net-(R21-T2)") (class "Default")
      (node (ref "R21") (pin "2") (pinfunction "T2_2") (pintype "passive"))
      (node (ref "U7") (pin "40") (pinfunction "TST_40") (pintype "passive"))
    )
    (net (code "63") (name "SPI_MISO") (class "Default")
      (node (ref "U7") (pin "27") (pinfunction "PA12_/_PGMD0_27") (pintype "bidirectional"))
    )
    (net (code "64") (name "SPI_SPCK") (class "Default")
      (node (ref "U7") (pin "21") (pinfunction "PA14_/_PGMD2_21") (pintype "bidirectional"))
    )
    (net (code "65") (name "unconnected-(J7-Pad4)") (class "Default")
      (node (ref "J7") (pin "4") (pinfunction "4_4") (pintype "passive"))
    )
    (net (code "66") (name "unconnected-(J8-Pad3)") (class "Default")
      (node (ref "J8") (pin "3") (pinfunction "3_3") (pintype "passive"))
    )
    (net (code "67") (name "unconnected-(U9-NC-Pad5)") (class "Default")
      (node (ref "U9") (pin "5") (pinfunction "NC_5") (pintype "passive"))
    )
  )
)
